# Sheet2.net
KiCad netlist of a schematic drawn in Altium Designer
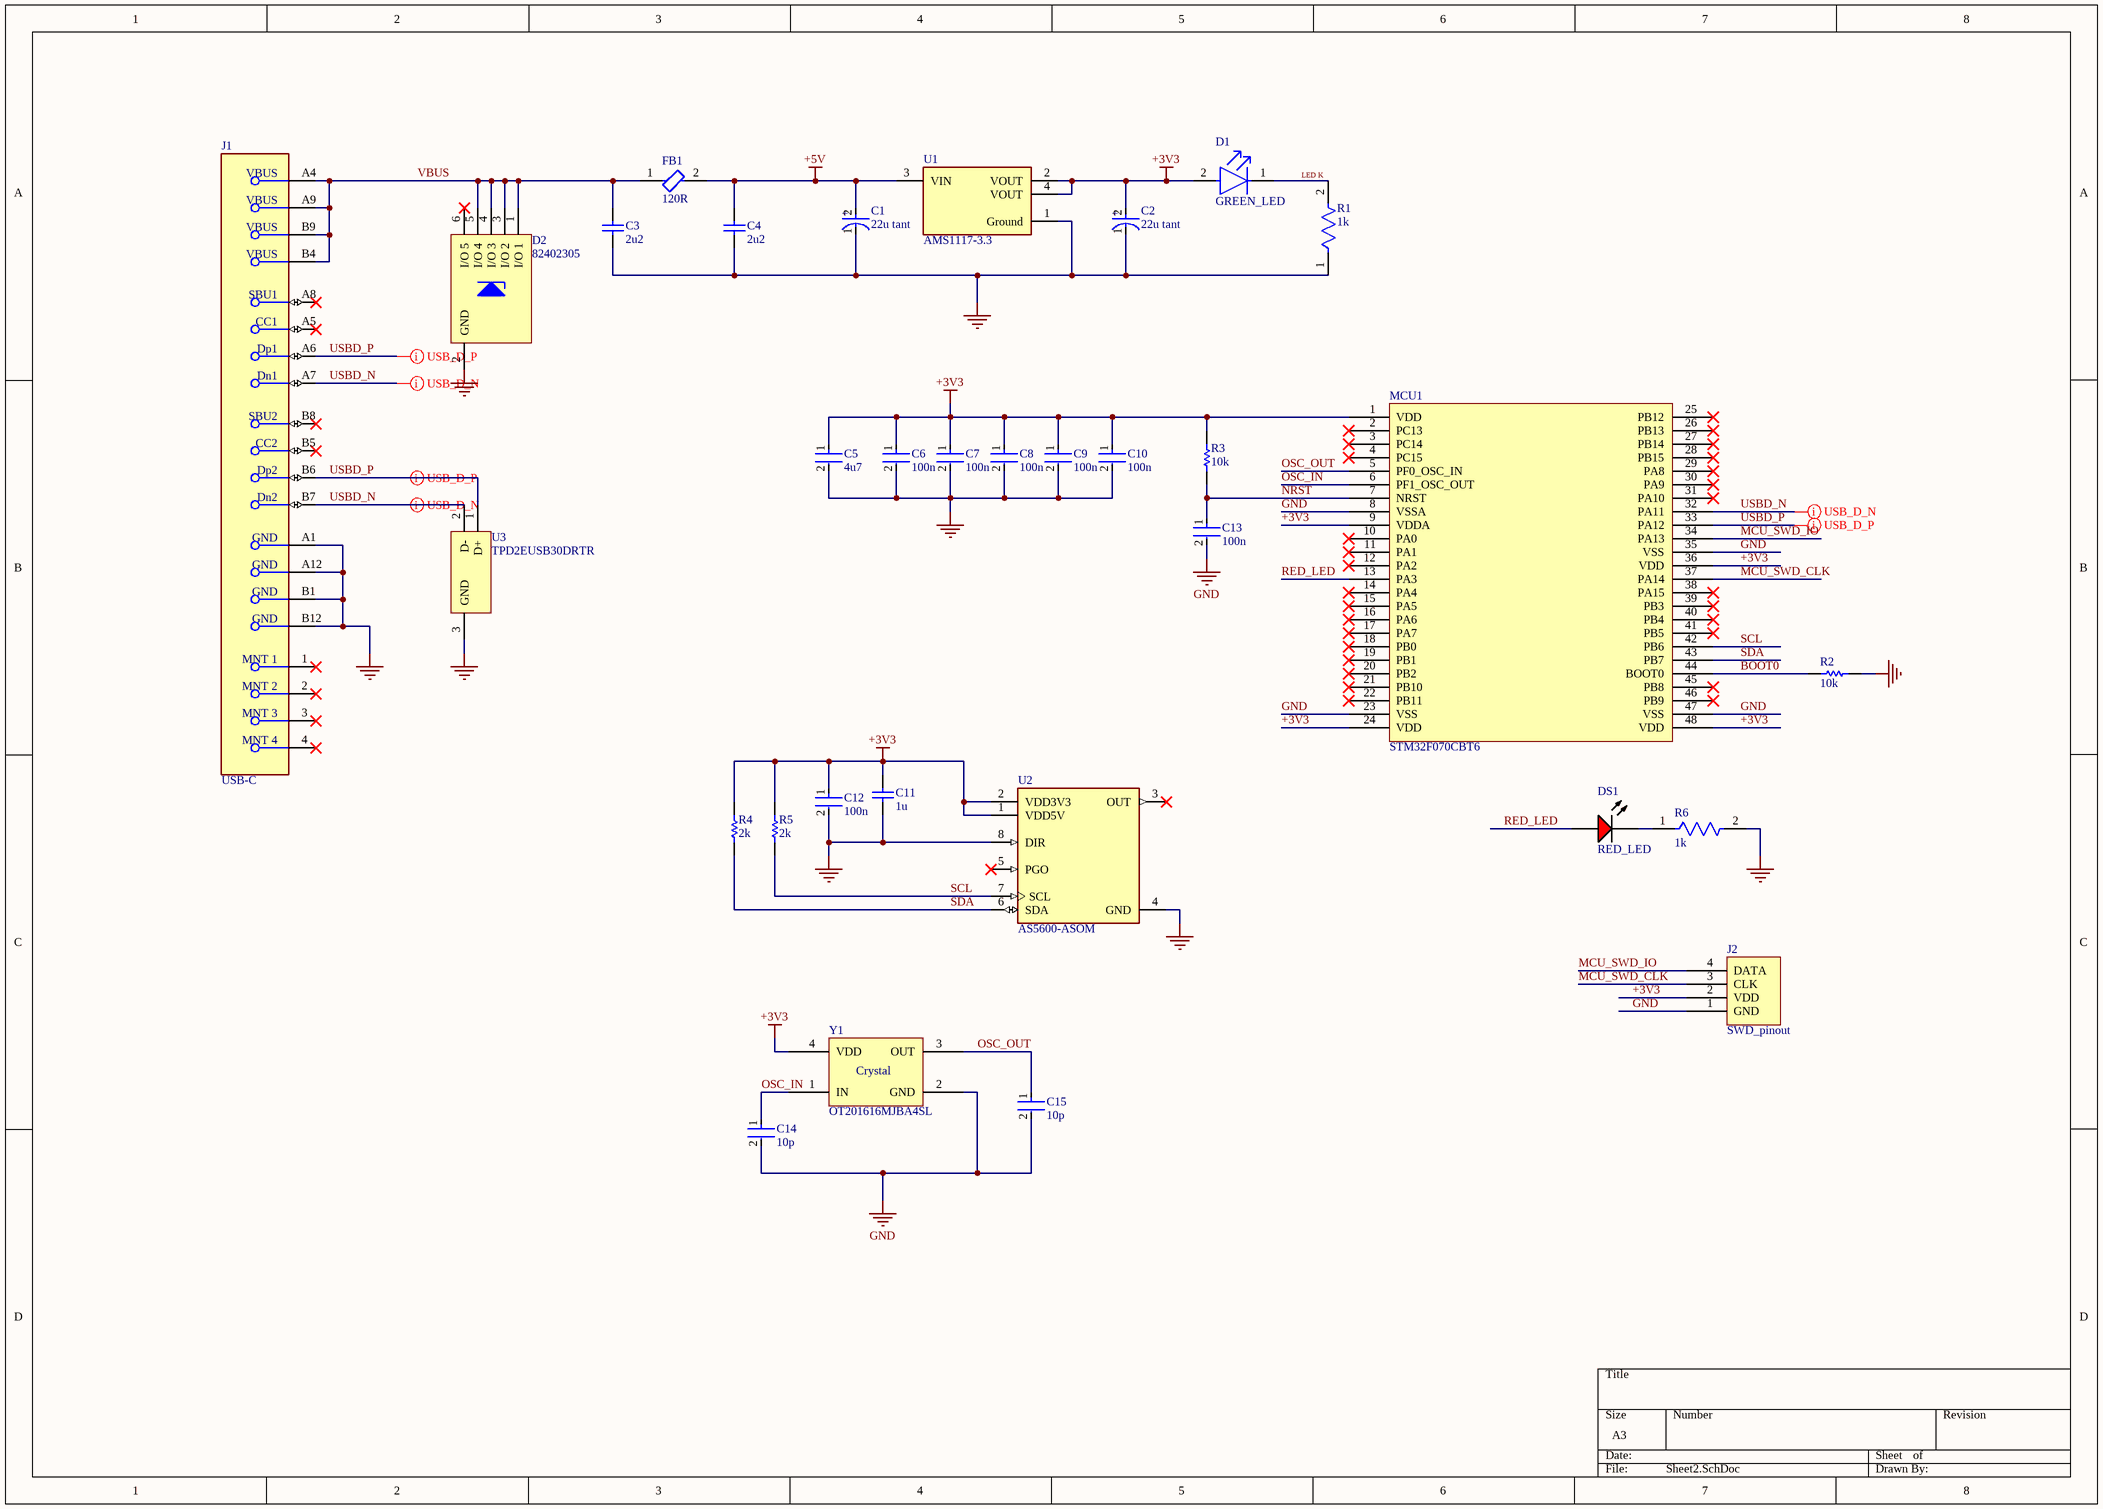
[diagram p0: Sheet2.SchDoc]

(export (version "E")
  (design (tool "Eeschema 10.0.6"))
  (components
    (comp (ref "C1")
      (value "22u tant")
      (footprint "FP-TAJB-MFG")
      (description "22uF 16V  ±10% 2.3Ω 1210  SMD Tantalum Capacitor")
      (fields (field (name "VOLTAGE") "16V") (field (name "TOLERANCE") "10%"))
      (libsource (lib "Altium Content Vault") (part "203bc49f2ac43e59fd269a8c329ed05"))
    )
    (comp (ref "C2")
      (value "22u tant")
      (footprint "FP-TAJB-MFG")
      (description "22uF 16V  ±10% 2.3Ω 1210  SMD Tantalum Capacitor")
      (fields (field (name "VOLTAGE") "16V") (field (name "TOLERANCE") "10%"))
      (libsource (lib "Altium Content Vault") (part "203bc49f2ac43e59fd269a8c329ed05"))
    )
    (comp (ref "C3")
      (value "2u2")
      (footprint "CAPC3216X180X50LL20T25")
      (description "Chip Capacitor, 2.2 uF, +/- 10%, 50 V, -55 to 125 degC, 1206 (3216 Metric), RoHS, Tape and Reel")
      (fields (field (name "MANUFACTURER") "Kemet") (field (name "TOLERANCE") "10%"))
      (libsource (lib "Altium Content Vault") (part "CAP-NP-2"))
    )
    (comp (ref "C4")
      (value "2u2")
      (footprint "CAPC3216X180X50LL20T25")
      (description "Chip Capacitor, 2.2 uF, +/- 10%, 50 V, -55 to 125 degC, 1206 (3216 Metric), RoHS, Tape and Reel")
      (fields (field (name "MANUFACTURER") "Kemet") (field (name "TOLERANCE") "10%"))
      (libsource (lib "Altium Content Vault") (part "CAP-NP-2"))
    )
    (comp (ref "C5")
      (value "4u7")
      (footprint "FP-C2012-125-0_2-IPC_B")
      (description "Multilayer Ceramic Capacitors 4.7μF ±10% 50V X5R SMD 0805")
      (fields (field (name "VOLTAGE") "50V") (field (name "TOLERANCE") "10%"))
      (libsource (lib "Altium Content Vault") (part "b4654b650e69147ec39a6b967a45e02"))
    )
    (comp (ref "C6")
      (value "100n")
      (footprint "FP-C0402-BB-MFG")
      (description "CAP CER 0.1UF 10V X5R 0402")
      (fields (field (name "MANUFACTURER") "Kemet") (field (name "TOLERANCE") "0.1"))
      (libsource (lib "Altium Content Vault") (part "b4654b650e69147ec39a6b967a45e02"))
    )
    (comp (ref "C7")
      (value "100n")
      (footprint "FP-C0402-BB-MFG")
      (description "CAP CER 0.1UF 10V X5R 0402")
      (fields (field (name "MANUFACTURER") "Kemet") (field (name "TOLERANCE") "0.1"))
      (libsource (lib "Altium Content Vault") (part "b4654b650e69147ec39a6b967a45e02"))
    )
    (comp (ref "C8")
      (value "100n")
      (footprint "FP-C0402-BB-MFG")
      (description "CAP CER 0.1UF 10V X5R 0402")
      (fields (field (name "MANUFACTURER") "Kemet") (field (name "TOLERANCE") "0.1"))
      (libsource (lib "Altium Content Vault") (part "b4654b650e69147ec39a6b967a45e02"))
    )
    (comp (ref "C9")
      (value "100n")
      (footprint "FP-C0402-BB-MFG")
      (description "CAP CER 0.1UF 10V X5R 0402")
      (fields (field (name "MANUFACTURER") "Kemet") (field (name "TOLERANCE") "0.1"))
      (libsource (lib "Altium Content Vault") (part "b4654b650e69147ec39a6b967a45e02"))
    )
    (comp (ref "C10")
      (value "100n")
      (footprint "FP-C0402-BB-MFG")
      (description "CAP CER 0.1UF 10V X5R 0402")
      (fields (field (name "MANUFACTURER") "Kemet") (field (name "TOLERANCE") "0.1"))
      (libsource (lib "Altium Content Vault") (part "b4654b650e69147ec39a6b967a45e02"))
    )
    (comp (ref "C11")
      (value "1u")
      (footprint "CAPC1608X87X35LL15T15")
      (fields (field (name "PART NUMBER") "C0603C105K3RACTU") (field (name "MANUFACTURER") "Kemet"))
      (libsource (lib "Altium Content Vault") (part "CAP"))
    )
    (comp (ref "C12")
      (value "100n")
      (footprint "FP-C0402-BB-MFG")
      (description "CAP CER 0.1UF 10V X5R 0402")
      (fields (field (name "MANUFACTURER") "Kemet") (field (name "TOLERANCE") "0.1"))
      (libsource (lib "Altium Content Vault") (part "b4654b650e69147ec39a6b967a45e02"))
    )
    (comp (ref "C13")
      (value "100n")
      (footprint "FP-C0402-BB-MFG")
      (description "CAP CER 0.1UF 10V X5R 0402")
      (fields (field (name "MANUFACTURER") "Kemet") (field (name "TOLERANCE") "0.1"))
      (libsource (lib "Altium Content Vault") (part "b4654b650e69147ec39a6b967a45e02"))
    )
    (comp (ref "C14")
      (value "10p")
      (footprint "FP-C0402-BB-MFG")
      (fields
        (field (name "MANUFACTURER PART NUMBER") "C0402C100J5GACTU")
        (field (name "MANUFACTURER") "Kemet")
        (field (name "OCTOPART") "https://octopart.com/c0402c100j5gactu-kemet-108448")
      )
      (libsource (lib "Altium Content Vault") (part "b4654b650e69147ec39a6b967a45e02"))
    )
    (comp (ref "C15")
      (value "10p")
      (footprint "FP-C0402-BB-MFG")
      (fields
        (field (name "MANUFACTURER PART NUMBER") "C0402C100J5GACTU")
        (field (name "MANUFACTURER") "Kemet")
        (field (name "OCTOPART") "https://octopart.com/c0402c100j5gactu-kemet-108448")
      )
      (libsource (lib "Altium Content Vault") (part "b4654b650e69147ec39a6b967a45e02"))
    )
    (comp (ref "D1")
      (value "GREEN_LED")
      (footprint "FP-LTST-C190GKT-MFG")
      (description "LED GREEN CLEAR CHIP SMD")
      (fields (field (name "VOLTAGE") "2V"))
      (libsource (lib "Altium Content Vault") (part "8706943c75ba83719d021d2fdc84c58"))
    )
    (comp (ref "D2")
      (value "82402305")
      (footprint "WE-TVS_SOT23-6L")
      (libsource (lib "Altium Content Vault") (part "Diode_5 Channel_Unidirectional - 82402305"))
    )
    (comp (ref "DS1")
      (value "RED_LED")
      (footprint "VISH-TLMX1100_V")
      (description "LED, RED, 2.1 V, -40 to 100 degC, 2-Pin SMD (0603), RoHS, Tape and Reel")
      (fields (field (name "TOLERANCE") "5%"))
      (libsource (lib "Altium Content Vault") (part "LED-RED-AK-2"))
    )
    (comp (ref "FB1")
      (value "120R")
      (footprint "FP-BLM21-0_2-t0_85-e0_5-d-IPC_C")
      (description "Chip Ferrite Bead, 0805, 120Ω @ 100MHz, 0.03Ω, 25%, 3A")
      (fields (field (name "TOLERANCE") "25%"))
      (libsource (lib "Altium Content Vault") (part "5f30dd21d616792df468990f7003faa"))
    )
    (comp (ref "J1")
      (value "USB-C")
      (footprint "FP-USB4085-GF-A-MFG")
      (description "CONN RCPT USB2.0 TYPE C 24POS RA")
      (libsource (lib "Altium Content Vault") (part "10fa745527c8b974685cbca3c197132"))
    )
    (comp (ref "J2")
      (value "SWD_pinout")
      (footprint "SWD_pinout")
      (libsource (lib "Schlib1") (part "SWD_pinout"))
    )
    (comp (ref "MCU1")
      (value "STM32F070CBT6")
      (footprint "STM32F070CBT6")
      (libsource (lib "Schlib1") (part "STM32F070CBT6"))
    )
    (comp (ref "R1")
      (value "1k")
      (footprint "FP-CRCW0603-e3-MFG")
      (description "RES Thick Film, 200Ω, 1%, 0.1W, 100ppm/°C, 0603")
      (fields (field (name "TOLERANCE") "1%"))
      (libsource (lib "Altium Content Vault") (part "1029c3af85768c4190bb7ad29bc67b5"))
    )
    (comp (ref "R2")
      (value "10k")
      (footprint "RESC1609X50X30NL8T20")
      (description "Chip Resistor, 10 KOhm, +/- 1%, 100 mW, -55 to 155 degC, 0603 (1608 Metric), RoHS, Tape and Reel")
      (fields (field (name "MANUFACTURER") "Vishay Semiconductor"))
      (libsource (lib "Altium Content Vault") (part "RES-2"))
    )
    (comp (ref "R3")
      (value "10k")
      (footprint "RESC1609X50X30NL8T20")
      (description "Chip Resistor, 10 KOhm, +/- 1%, 100 mW, -55 to 155 degC, 0603 (1608 Metric), RoHS, Tape and Reel")
      (fields (field (name "MANUFACTURER") "Vishay Semiconductor"))
      (libsource (lib "Altium Content Vault") (part "RES-2"))
    )
    (comp (ref "R4")
      (value "2k")
      (footprint "RESC1608X55X25LL10T15")
      (description "Chip Resistor, 4.7 KOhm, +/- 1%, 0.1 W, -55 to 155 degC, 0603 (1608 Metric), RoHS, Tape and Reel")
      (fields (field (name "MANUFACTURER") "Yageo") (field (name "TOLERANCE") "1%"))
      (libsource (lib "Altium Content Vault") (part "RES-2"))
    )
    (comp (ref "R5")
      (value "2k")
      (footprint "RESC1608X55X25LL10T15")
      (description "Chip Resistor, 4.7 KOhm, +/- 1%, 0.1 W, -55 to 155 degC, 0603 (1608 Metric), RoHS, Tape and Reel")
      (fields (field (name "MANUFACTURER") "Yageo") (field (name "TOLERANCE") "1%"))
      (libsource (lib "Altium Content Vault") (part "RES-2"))
    )
    (comp (ref "R6")
      (value "1k")
      (footprint "FP-RC0603-0_55-MFG")
      (fields (field (name "TOLERANCE") "1%"))
      (libsource (lib "Altium Content Vault") (part "1029c3af85768c4190bb7ad29bc67b5"))
    )
    (comp (ref "U1")
      (value "AMS1117-3.3")
      (footprint "FP-AMS1117-IPC_C")
      (description "LDO Voltage Regulators 1A, 3.3V")
      (fields
        (field (name "OCTOPART") "https://octopart.com/ams1117-3.3-advanced+monolithic+systems-25899300")
        (field (name "MANUFACTURER") "Advanced Monolithic Systems")
      )
      (libsource (lib "Altium Content Vault") (part "8bdbb5f8e77002000e30dd2845d0354"))
    )
    (comp (ref "U2")
      (value "AS5600-ASOM")
      (footprint "FP-AS5600-ASOM-IPC_C")
      (description "SENSOR ANGLE 360DEG SMD")
      (libsource (lib "Altium Content Vault") (part "7a1e9824f8ff8a913d90a1366781b5b"))
    )
    (comp (ref "U3")
      (value "TPD2EUSB30DRTR")
      (footprint "DRT0003A")
      (fields (field (name "MANUFACTURER") "Texas Instruments"))
      (libsource (lib "Altium Content Vault") (part "TI-TPD2EUSB30-SOT_DRT-3"))
    )
    (comp (ref "Y1")
      (value "OT201616MJBA4SL")
      (footprint "OT201616MJBA4SL")
      (libsource (lib "Schlib1") (part "OT201616MJBA4SL"))
    )
  )
  (nets
    (net (code "1") (name "+3V3") (class "Default")
      (node (ref "C10") (pin "1") (pinfunction "1_1") (pintype "passive"))
      (node (ref "C11") (pin "2") (pinfunction "2_2") (pintype "passive"))
      (node (ref "C12") (pin "1") (pinfunction "1_1") (pintype "passive"))
      (node (ref "C2") (pin "2") (pinfunction "A_2") (pintype "passive"))
      (node (ref "C5") (pin "1") (pinfunction "1_1") (pintype "passive"))
      (node (ref "C6") (pin "1") (pinfunction "1_1") (pintype "passive"))
      (node (ref "C7") (pin "1") (pinfunction "1_1") (pintype "passive"))
      (node (ref "C8") (pin "1") (pinfunction "1_1") (pintype "passive"))
      (node (ref "C9") (pin "1") (pinfunction "1_1") (pintype "passive"))
      (node (ref "D1") (pin "2") (pinfunction "A_2") (pintype "passive"))
      (node (ref "J2") (pin "2") (pinfunction "VDD_2") (pintype "passive"))
      (node (ref "MCU1") (pin "1") (pinfunction "VDD_1") (pintype "passive"))
      (node (ref "MCU1") (pin "24") (pinfunction "VDD_24") (pintype "passive"))
      (node (ref "MCU1") (pin "36") (pinfunction "VDD_36") (pintype "passive"))
      (node (ref "MCU1") (pin "48") (pinfunction "VDD_48") (pintype "passive"))
      (node (ref "MCU1") (pin "9") (pinfunction "VDDA_9") (pintype "passive"))
      (node (ref "R3") (pin "1") (pinfunction "1_1") (pintype "passive"))
      (node (ref "R4") (pin "2") (pinfunction "2_2") (pintype "passive"))
      (node (ref "R5") (pin "2") (pinfunction "2_2") (pintype "passive"))
      (node (ref "U1") (pin "2") (pinfunction "VOUT_2") (pintype "passive"))
      (node (ref "U1") (pin "4") (pinfunction "VOUT_4") (pintype "passive"))
      (node (ref "U2") (pin "1") (pinfunction "VDD5V_1") (pintype "power_in"))
      (node (ref "U2") (pin "2") (pinfunction "VDD3V3_2") (pintype "power_in"))
      (node (ref "Y1") (pin "4") (pinfunction "VDD_4") (pintype "passive"))
    )
    (net (code "2") (name "+5V") (class "Default")
      (node (ref "C1") (pin "2") (pinfunction "A_2") (pintype "passive"))
      (node (ref "C4") (pin "2") (pinfunction "2_2") (pintype "passive"))
      (node (ref "FB1") (pin "2") (pinfunction "2_2") (pintype "passive"))
      (node (ref "U1") (pin "3") (pinfunction "VIN_3") (pintype "power_in"))
    )
    (net (code "3") (name "/BOOT0") (class "Default")
      (node (ref "MCU1") (pin "44") (pinfunction "BOOT0_44") (pintype "passive"))
      (node (ref "R2") (pin "2") (pinfunction "2_2") (pintype "passive"))
    )
    (net (code "4") (name "/LED K") (class "Default")
      (node (ref "D1") (pin "1") (pinfunction "C_1") (pintype "passive"))
      (node (ref "R1") (pin "2") (pinfunction "2_2") (pintype "passive"))
    )
    (net (code "5") (name "/MCU_SWD_CLK") (class "Default")
      (node (ref "J2") (pin "3") (pinfunction "CLK_3") (pintype "passive"))
      (node (ref "MCU1") (pin "37") (pinfunction "PA14_37") (pintype "passive"))
    )
    (net (code "6") (name "/MCU_SWD_IO") (class "Default")
      (node (ref "J2") (pin "4") (pinfunction "DATA_4") (pintype "passive"))
      (node (ref "MCU1") (pin "34") (pinfunction "PA13_34") (pintype "passive"))
    )
    (net (code "7") (name "/NRST") (class "Default")
      (node (ref "C13") (pin "1") (pinfunction "1_1") (pintype "passive"))
      (node (ref "MCU1") (pin "7") (pinfunction "NRST_7") (pintype "passive"))
      (node (ref "R3") (pin "2") (pinfunction "2_2") (pintype "passive"))
    )
    (net (code "8") (name "/OSC_IN") (class "Default")
      (node (ref "C14") (pin "1") (pinfunction "1_1") (pintype "passive"))
      (node (ref "MCU1") (pin "6") (pinfunction "PF1_OSC_OUT_6") (pintype "passive"))
      (node (ref "Y1") (pin "1") (pinfunction "IN_1") (pintype "passive"))
    )
    (net (code "9") (name "/OSC_OUT") (class "Default")
      (node (ref "C15") (pin "1") (pinfunction "1_1") (pintype "passive"))
      (node (ref "MCU1") (pin "5") (pinfunction "PF0_OSC_IN_5") (pintype "passive"))
      (node (ref "Y1") (pin "3") (pinfunction "OUT_3") (pintype "passive"))
    )
    (net (code "10") (name "/RED_LED") (class "Default")
      (node (ref "DS1") (pin "1") (pinfunction "A_1") (pintype "passive"))
      (node (ref "MCU1") (pin "13") (pinfunction "PA3_13") (pintype "passive"))
    )
    (net (code "11") (name "/SCL") (class "Default")
      (node (ref "MCU1") (pin "42") (pinfunction "PB6_42") (pintype "passive"))
      (node (ref "R5") (pin "1") (pinfunction "1_1") (pintype "passive"))
      (node (ref "U2") (pin "7") (pinfunction "SCL_7") (pintype "input"))
    )
    (net (code "12") (name "/SDA") (class "Default")
      (node (ref "MCU1") (pin "43") (pinfunction "PB7_43") (pintype "passive"))
      (node (ref "R4") (pin "1") (pinfunction "1_1") (pintype "passive"))
      (node (ref "U2") (pin "6") (pinfunction "SDA_6") (pintype "bidirectional"))
    )
    (net (code "13") (name "/USBD_N") (class "Default")
      (node (ref "J1") (pin "A7") (pinfunction "Dn1_A7") (pintype "bidirectional"))
      (node (ref "J1") (pin "B7") (pinfunction "Dn2_B7") (pintype "bidirectional"))
      (node (ref "MCU1") (pin "32") (pinfunction "PA11_32") (pintype "passive"))
      (node (ref "U3") (pin "2") (pinfunction "D-_2") (pintype "passive"))
    )
    (net (code "14") (name "/USBD_P") (class "Default")
      (node (ref "J1") (pin "A6") (pinfunction "Dp1_A6") (pintype "bidirectional"))
      (node (ref "J1") (pin "B6") (pinfunction "Dp2_B6") (pintype "bidirectional"))
      (node (ref "MCU1") (pin "33") (pinfunction "PA12_33") (pintype "passive"))
      (node (ref "U3") (pin "1") (pinfunction "D+_1") (pintype "passive"))
    )
    (net (code "15") (name "/VBUS") (class "Default")
      (node (ref "C3") (pin "2") (pinfunction "2_2") (pintype "passive"))
      (node (ref "D2") (pin "1") (pinfunction "I/O_1_1") (pintype "passive"))
      (node (ref "D2") (pin "3") (pinfunction "I/O_2_3") (pintype "passive"))
      (node (ref "D2") (pin "4") (pinfunction "I/O_3_4") (pintype "passive"))
      (node (ref "D2") (pin "5") (pinfunction "I/O_4_5") (pintype "passive"))
      (node (ref "FB1") (pin "1") (pinfunction "1_1") (pintype "passive"))
      (node (ref "J1") (pin "A4") (pinfunction "VBUS_A4") (pintype "power_in"))
      (node (ref "J1") (pin "A9") (pinfunction "VBUS_A9") (pintype "power_in"))
      (node (ref "J1") (pin "B4") (pinfunction "VBUS_B4") (pintype "power_in"))
      (node (ref "J1") (pin "B9") (pinfunction "VBUS_B9") (pintype "power_in"))
    )
    (net (code "16") (name "GND") (class "Default")
      (node (ref "C1") (pin "1") (pinfunction "C_1") (pintype "passive"))
      (node (ref "C10") (pin "2") (pinfunction "2_2") (pintype "passive"))
      (node (ref "C11") (pin "1") (pinfunction "1_1") (pintype "passive"))
      (node (ref "C12") (pin "2") (pinfunction "2_2") (pintype "passive"))
      (node (ref "C13") (pin "2") (pinfunction "2_2") (pintype "passive"))
      (node (ref "C14") (pin "2") (pinfunction "2_2") (pintype "passive"))
      (node (ref "C15") (pin "2") (pinfunction "2_2") (pintype "passive"))
      (node (ref "C2") (pin "1") (pinfunction "C_1") (pintype "passive"))
      (node (ref "C3") (pin "1") (pinfunction "1_1") (pintype "passive"))
      (node (ref "C4") (pin "1") (pinfunction "1_1") (pintype "passive"))
      (node (ref "C5") (pin "2") (pinfunction "2_2") (pintype "passive"))
      (node (ref "C6") (pin "2") (pinfunction "2_2") (pintype "passive"))
      (node (ref "C7") (pin "2") (pinfunction "2_2") (pintype "passive"))
      (node (ref "C8") (pin "2") (pinfunction "2_2") (pintype "passive"))
      (node (ref "C9") (pin "2") (pinfunction "2_2") (pintype "passive"))
      (node (ref "D2") (pin "2") (pinfunction "GND_2") (pintype "passive"))
      (node (ref "J1") (pin "A1") (pinfunction "GND_A1") (pintype "power_in"))
      (node (ref "J1") (pin "A12") (pinfunction "GND_A12") (pintype "power_in"))
      (node (ref "J1") (pin "B1") (pinfunction "GND_B1") (pintype "power_in"))
      (node (ref "J1") (pin "B12") (pinfunction "GND_B12") (pintype "power_in"))
      (node (ref "J2") (pin "1") (pinfunction "GND_1") (pintype "passive"))
      (node (ref "MCU1") (pin "23") (pinfunction "VSS_23") (pintype "passive"))
      (node (ref "MCU1") (pin "35") (pinfunction "VSS_35") (pintype "passive"))
      (node (ref "MCU1") (pin "47") (pinfunction "VSS_47") (pintype "passive"))
      (node (ref "MCU1") (pin "8") (pinfunction "VSSA_8") (pintype "passive"))
      (node (ref "R1") (pin "1") (pinfunction "1_1") (pintype "passive"))
      (node (ref "R2") (pin "1") (pinfunction "1_1") (pintype "passive"))
      (node (ref "R6") (pin "2") (pinfunction "2_2") (pintype "passive"))
      (node (ref "U1") (pin "1") (pinfunction "Ground_1") (pintype "power_in"))
      (node (ref "U2") (pin "4") (pinfunction "GND_4") (pintype "power_in"))
      (node (ref "U2") (pin "8") (pinfunction "DIR_8") (pintype "input"))
      (node (ref "U3") (pin "3") (pinfunction "GND_3") (pintype "power_in"))
      (node (ref "Y1") (pin "2") (pinfunction "GND_2") (pintype "passive"))
    )
    (net (code "17") (name "Net-(DS1-K)") (class "Default")
      (node (ref "DS1") (pin "2") (pinfunction "K_2") (pintype "passive"))
      (node (ref "R6") (pin "1") (pinfunction "1_1") (pintype "passive"))
    )
    (net (code "18") (name "unconnected-(D2-I{slash}O_5-Pad6)") (class "Default")
      (node (ref "D2") (pin "6") (pinfunction "I/O_5_6") (pintype "passive+no_connect"))
    )
    (net (code "19") (name "unconnected-(J1-CC1-PadA5)") (class "Default")
      (node (ref "J1") (pin "A5") (pinfunction "CC1_A5") (pintype "bidirectional+no_connect"))
    )
    (net (code "20") (name "unconnected-(J1-CC2-PadB5)") (class "Default")
      (node (ref "J1") (pin "B5") (pinfunction "CC2_B5") (pintype "bidirectional+no_connect"))
    )
    (net (code "21") (name "unconnected-(J1-MNT_1-Pad1)") (class "Default")
      (node (ref "J1") (pin "1") (pinfunction "MNT_1_1") (pintype "passive+no_connect"))
    )
    (net (code "22") (name "unconnected-(J1-MNT_2-Pad2)") (class "Default")
      (node (ref "J1") (pin "2") (pinfunction "MNT_2_2") (pintype "passive+no_connect"))
    )
    (net (code "23") (name "unconnected-(J1-MNT_3-Pad3)") (class "Default")
      (node (ref "J1") (pin "3") (pinfunction "MNT_3_3") (pintype "passive+no_connect"))
    )
    (net (code "24") (name "unconnected-(J1-MNT_4-Pad4)") (class "Default")
      (node (ref "J1") (pin "4") (pinfunction "MNT_4_4") (pintype "passive+no_connect"))
    )
    (net (code "25") (name "unconnected-(J1-SBU1-PadA8)") (class "Default")
      (node (ref "J1") (pin "A8") (pinfunction "SBU1_A8") (pintype "bidirectional+no_connect"))
    )
    (net (code "26") (name "unconnected-(J1-SBU2-PadB8)") (class "Default")
      (node (ref "J1") (pin "B8") (pinfunction "SBU2_B8") (pintype "bidirectional+no_connect"))
    )
    (net (code "27") (name "unconnected-(MCU1-PA0-Pad10)") (class "Default")
      (node (ref "MCU1") (pin "10") (pinfunction "PA0_10") (pintype "passive+no_connect"))
    )
    (net (code "28") (name "unconnected-(MCU1-PA1-Pad11)") (class "Default")
      (node (ref "MCU1") (pin "11") (pinfunction "PA1_11") (pintype "passive+no_connect"))
    )
    (net (code "29") (name "unconnected-(MCU1-PA2-Pad12)") (class "Default")
      (node (ref "MCU1") (pin "12") (pinfunction "PA2_12") (pintype "passive+no_connect"))
    )
    (net (code "30") (name "unconnected-(MCU1-PA4-Pad14)") (class "Default")
      (node (ref "MCU1") (pin "14") (pinfunction "PA4_14") (pintype "passive+no_connect"))
    )
    (net (code "31") (name "unconnected-(MCU1-PA5-Pad15)") (class "Default")
      (node (ref "MCU1") (pin "15") (pinfunction "PA5_15") (pintype "passive+no_connect"))
    )
    (net (code "32") (name "unconnected-(MCU1-PA6-Pad16)") (class "Default")
      (node (ref "MCU1") (pin "16") (pinfunction "PA6_16") (pintype "passive+no_connect"))
    )
    (net (code "33") (name "unconnected-(MCU1-PA7-Pad17)") (class "Default")
      (node (ref "MCU1") (pin "17") (pinfunction "PA7_17") (pintype "passive+no_connect"))
    )
    (net (code "34") (name "unconnected-(MCU1-PA8-Pad29)") (class "Default")
      (node (ref "MCU1") (pin "29") (pinfunction "PA8_29") (pintype "passive+no_connect"))
    )
    (net (code "35") (name "unconnected-(MCU1-PA9-Pad30)") (class "Default")
      (node (ref "MCU1") (pin "30") (pinfunction "PA9_30") (pintype "passive+no_connect"))
    )
    (net (code "36") (name "unconnected-(MCU1-PA10-Pad31)") (class "Default")
      (node (ref "MCU1") (pin "31") (pinfunction "PA10_31") (pintype "passive+no_connect"))
    )
    (net (code "37") (name "unconnected-(MCU1-PA15-Pad38)") (class "Default")
      (node (ref "MCU1") (pin "38") (pinfunction "PA15_38") (pintype "passive+no_connect"))
    )
    (net (code "38") (name "unconnected-(MCU1-PB0-Pad18)") (class "Default")
      (node (ref "MCU1") (pin "18") (pinfunction "PB0_18") (pintype "passive+no_connect"))
    )
    (net (code "39") (name "unconnected-(MCU1-PB1-Pad19)") (class "Default")
      (node (ref "MCU1") (pin "19") (pinfunction "PB1_19") (pintype "passive+no_connect"))
    )
    (net (code "40") (name "unconnected-(MCU1-PB2-Pad20)") (class "Default")
      (node (ref "MCU1") (pin "20") (pinfunction "PB2_20") (pintype "passive+no_connect"))
    )
    (net (code "41") (name "unconnected-(MCU1-PB3-Pad39)") (class "Default")
      (node (ref "MCU1") (pin "39") (pinfunction "PB3_39") (pintype "passive+no_connect"))
    )
    (net (code "42") (name "unconnected-(MCU1-PB4-Pad40)") (class "Default")
      (node (ref "MCU1") (pin "40") (pinfunction "PB4_40") (pintype "passive+no_connect"))
    )
    (net (code "43") (name "unconnected-(MCU1-PB5-Pad41)") (class "Default")
      (node (ref "MCU1") (pin "41") (pinfunction "PB5_41") (pintype "passive+no_connect"))
    )
    (net (code "44") (name "unconnected-(MCU1-PB8-Pad45)") (class "Default")
      (node (ref "MCU1") (pin "45") (pinfunction "PB8_45") (pintype "passive+no_connect"))
    )
    (net (code "45") (name "unconnected-(MCU1-PB9-Pad46)") (class "Default")
      (node (ref "MCU1") (pin "46") (pinfunction "PB9_46") (pintype "passive+no_connect"))
    )
    (net (code "46") (name "unconnected-(MCU1-PB10-Pad21)") (class "Default")
      (node (ref "MCU1") (pin "21") (pinfunction "PB10_21") (pintype "passive+no_connect"))
    )
    (net (code "47") (name "unconnected-(MCU1-PB11-Pad22)") (class "Default")
      (node (ref "MCU1") (pin "22") (pinfunction "PB11_22") (pintype "passive+no_connect"))
    )
    (net (code "48") (name "unconnected-(MCU1-PB12-Pad25)") (class "Default")
      (node (ref "MCU1") (pin "25") (pinfunction "PB12_25") (pintype "passive+no_connect"))
    )
    (net (code "49") (name "unconnected-(MCU1-PB13-Pad26)") (class "Default")
      (node (ref "MCU1") (pin "26") (pinfunction "PB13_26") (pintype "passive+no_connect"))
    )
    (net (code "50") (name "unconnected-(MCU1-PB14-Pad27)") (class "Default")
      (node (ref "MCU1") (pin "27") (pinfunction "PB14_27") (pintype "passive+no_connect"))
    )
    (net (code "51") (name "unconnected-(MCU1-PB15-Pad28)") (class "Default")
      (node (ref "MCU1") (pin "28") (pinfunction "PB15_28") (pintype "passive+no_connect"))
    )
    (net (code "52") (name "unconnected-(MCU1-PC13-Pad2)") (class "Default")
      (node (ref "MCU1") (pin "2") (pinfunction "PC13_2") (pintype "passive+no_connect"))
    )
    (net (code "53") (name "unconnected-(MCU1-PC14-Pad3)") (class "Default")
      (node (ref "MCU1") (pin "3") (pinfunction "PC14_3") (pintype "passive+no_connect"))
    )
    (net (code "54") (name "unconnected-(MCU1-PC15-Pad4)") (class "Default")
      (node (ref "MCU1") (pin "4") (pinfunction "PC15_4") (pintype "passive+no_connect"))
    )
    (net (code "55") (name "unconnected-(U2-OUT-Pad3)") (class "Default")
      (node (ref "U2") (pin "3") (pinfunction "OUT_3") (pintype "output+no_connect"))
    )
    (net (code "56") (name "unconnected-(U2-PGO-Pad5)") (class "Default")
      (node (ref "U2") (pin "5") (pinfunction "PGO_5") (pintype "input+no_connect"))
    )
  )
)
